# RASPBERRY_SHILED_ADS1299.net
KiCad netlist of a schematic drawn in Altium Designer
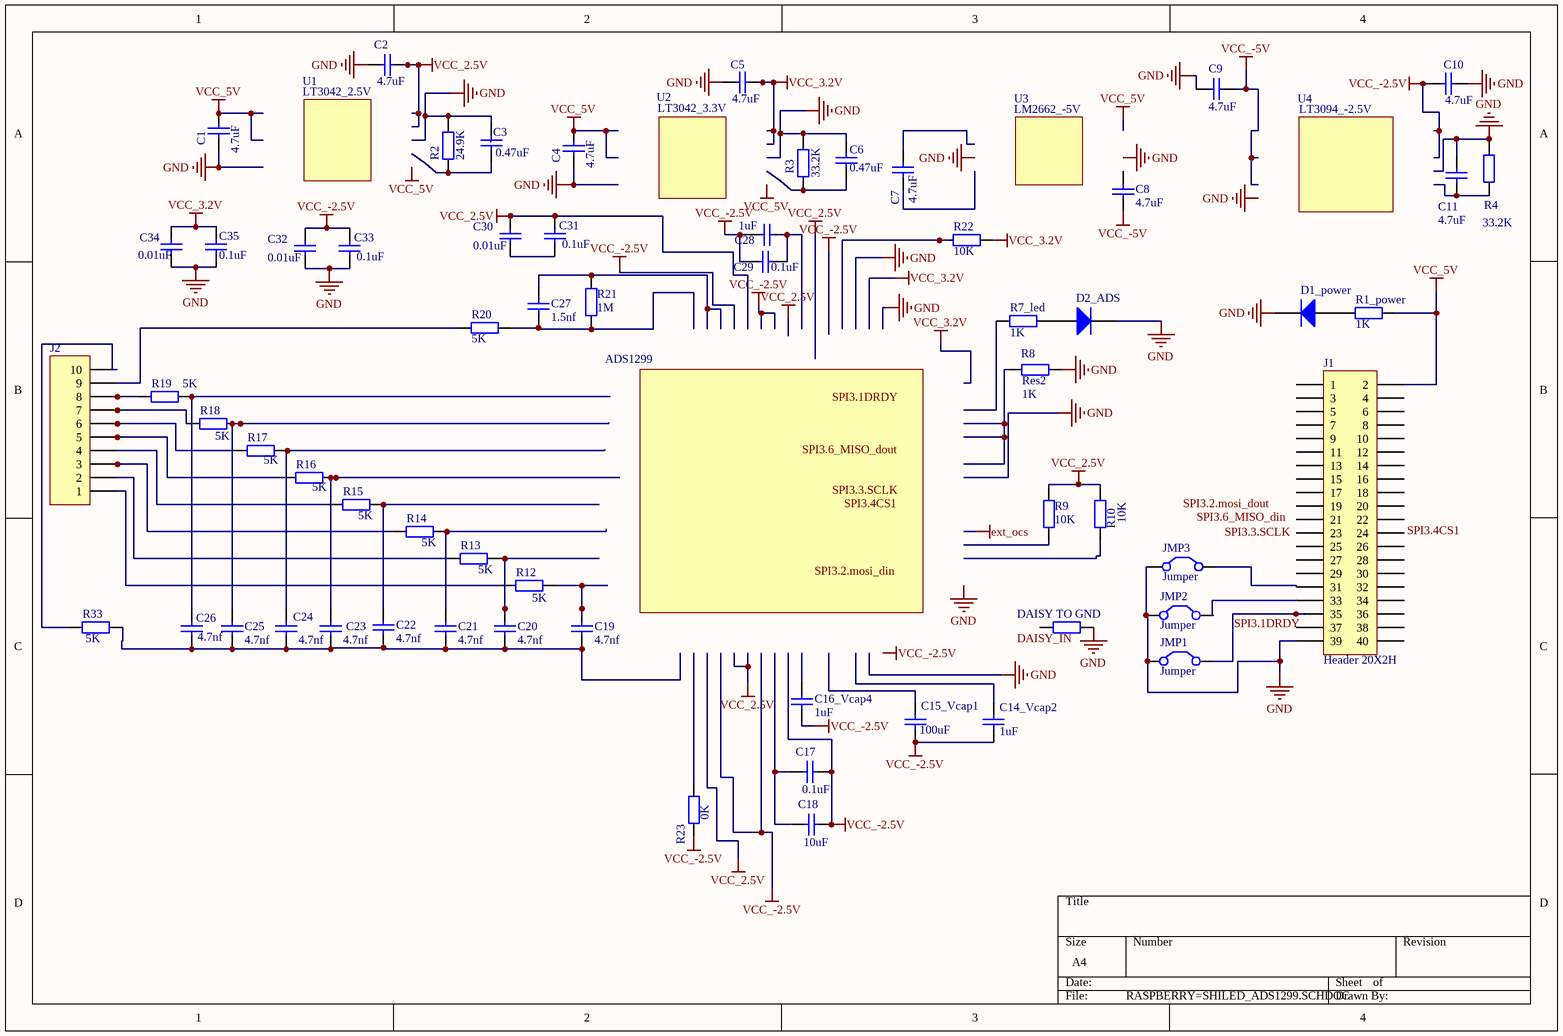
[diagram p0: RASPBERRY=SHILED_ADS1299.SCHDOC]

(export (version "E")
  (design (tool "Eeschema 10.0.6"))
  (components
    (comp (ref "C1")
      (value "4.7uF")
      (footprint "RAD-0.3")
      (description "Capacitor")
      (fields (field (name "PUBLISHER") "Altium Limited"))
      (libsource (lib "Miscellaneous Devices") (part "Cap"))
    )
    (comp (ref "C2")
      (value "4.7uF")
      (footprint "RAD-0.3")
      (description "Capacitor")
      (fields (field (name "PUBLISHER") "Altium Limited"))
      (libsource (lib "Miscellaneous Devices") (part "Cap"))
    )
    (comp (ref "C3")
      (value "0.47uF")
      (footprint "RAD-0.3")
      (description "Capacitor")
      (fields (field (name "PUBLISHER") "Altium Limited"))
      (libsource (lib "Miscellaneous Devices") (part "Cap"))
    )
    (comp (ref "C4")
      (value "4.7uF")
      (footprint "RAD-0.3")
      (description "Capacitor")
      (fields (field (name "PUBLISHER") "Altium Limited"))
      (libsource (lib "Miscellaneous Devices") (part "Cap"))
    )
    (comp (ref "C5")
      (value "4.7uF")
      (footprint "RAD-0.3")
      (description "Capacitor")
      (fields (field (name "PUBLISHER") "Altium Limited"))
      (libsource (lib "Miscellaneous Devices") (part "Cap"))
    )
    (comp (ref "C6")
      (value "0.47uF")
      (footprint "RAD-0.3")
      (description "Capacitor")
      (fields (field (name "PUBLISHER") "Altium Limited"))
      (libsource (lib "Miscellaneous Devices") (part "Cap"))
    )
    (comp (ref "C7")
      (value "4.7uF")
      (footprint "RAD-0.3")
      (description "Capacitor")
      (fields (field (name "PUBLISHER") "Altium Limited"))
      (libsource (lib "Miscellaneous Devices") (part "Cap"))
    )
    (comp (ref "C8")
      (value "4.7uF")
      (footprint "RAD-0.3")
      (description "Capacitor")
      (fields (field (name "PUBLISHER") "Altium Limited"))
      (libsource (lib "Miscellaneous Devices") (part "Cap"))
    )
    (comp (ref "C9")
      (value "4.7uF")
      (footprint "RAD-0.3")
      (description "Capacitor")
      (fields (field (name "PUBLISHER") "Altium Limited"))
      (libsource (lib "Miscellaneous Devices") (part "Cap"))
    )
    (comp (ref "C10")
      (value "4.7uF")
      (footprint "RAD-0.3")
      (description "Capacitor")
      (fields (field (name "PUBLISHER") "Altium Limited"))
      (libsource (lib "Miscellaneous Devices") (part "Cap"))
    )
    (comp (ref "C11")
      (value "4.7uF")
      (footprint "RAD-0.3")
      (description "Capacitor")
      (fields (field (name "PUBLISHER") "Altium Limited"))
      (libsource (lib "Miscellaneous Devices") (part "Cap"))
    )
    (comp (ref "C14_Vcap2")
      (value "1uF")
      (footprint "RAD-0.3")
      (description "Capacitor")
      (fields (field (name "PUBLISHER") "Altium Limited"))
      (libsource (lib "Miscellaneous Devices") (part "Cap"))
    )
    (comp (ref "C15_Vcap1")
      (value "100uF")
      (footprint "RAD-0.3")
      (description "Capacitor")
      (fields (field (name "PUBLISHER") "Altium Limited"))
      (libsource (lib "Miscellaneous Devices") (part "Cap"))
    )
    (comp (ref "C16_Vcap4")
      (value "1uF")
      (footprint "RAD-0.3")
      (description "Capacitor")
      (fields (field (name "PUBLISHER") "Altium Limited"))
      (libsource (lib "Miscellaneous Devices") (part "Cap"))
    )
    (comp (ref "C17")
      (value "0.1uF")
      (footprint "RAD-0.3")
      (description "Capacitor")
      (fields (field (name "PUBLISHER") "Altium Limited"))
      (libsource (lib "Miscellaneous Devices") (part "Cap"))
    )
    (comp (ref "C18")
      (value "10uF")
      (footprint "RAD-0.3")
      (description "Capacitor")
      (fields (field (name "PUBLISHER") "Altium Limited"))
      (libsource (lib "Miscellaneous Devices") (part "Cap"))
    )
    (comp (ref "C19")
      (value "4.7nf")
      (footprint "RAD-0.3")
      (description "Capacitor")
      (fields (field (name "PUBLISHER") "Altium Limited"))
      (libsource (lib "Miscellaneous Devices") (part "Cap"))
    )
    (comp (ref "C20")
      (value "4.7nf")
      (footprint "RAD-0.3")
      (description "Capacitor")
      (fields (field (name "PUBLISHER") "Altium Limited"))
      (libsource (lib "Miscellaneous Devices") (part "Cap"))
    )
    (comp (ref "C21")
      (value "4.7nf")
      (footprint "RAD-0.3")
      (description "Capacitor")
      (fields (field (name "PUBLISHER") "Altium Limited"))
      (libsource (lib "Miscellaneous Devices") (part "Cap"))
    )
    (comp (ref "C22")
      (value "4.7nf")
      (footprint "RAD-0.3")
      (description "Capacitor")
      (fields (field (name "PUBLISHER") "Altium Limited"))
      (libsource (lib "Miscellaneous Devices") (part "Cap"))
    )
    (comp (ref "C23")
      (value "4.7nf")
      (footprint "RAD-0.3")
      (description "Capacitor")
      (fields (field (name "PUBLISHER") "Altium Limited"))
      (libsource (lib "Miscellaneous Devices") (part "Cap"))
    )
    (comp (ref "C24")
      (value "4.7nf")
      (footprint "RAD-0.3")
      (description "Capacitor")
      (fields (field (name "PUBLISHER") "Altium Limited"))
      (libsource (lib "Miscellaneous Devices") (part "Cap"))
    )
    (comp (ref "C25")
      (value "4.7nf")
      (footprint "RAD-0.3")
      (description "Capacitor")
      (fields (field (name "PUBLISHER") "Altium Limited"))
      (libsource (lib "Miscellaneous Devices") (part "Cap"))
    )
    (comp (ref "C26")
      (value "4.7nf")
      (footprint "RAD-0.3")
      (description "Capacitor")
      (fields (field (name "PUBLISHER") "Altium Limited"))
      (libsource (lib "Miscellaneous Devices") (part "Cap"))
    )
    (comp (ref "C27")
      (value "1.5nf")
      (footprint "RAD-0.3")
      (description "Capacitor")
      (fields (field (name "PUBLISHER") "Altium Limited"))
      (libsource (lib "Miscellaneous Devices") (part "Cap"))
    )
    (comp (ref "C28")
      (value "1uF")
      (footprint "RAD-0.3")
      (description "Capacitor")
      (fields (field (name "PUBLISHER") "Altium Limited"))
      (libsource (lib "Miscellaneous Devices") (part "Cap"))
    )
    (comp (ref "C29")
      (value "0.1uF")
      (footprint "RAD-0.3")
      (description "Capacitor")
      (fields (field (name "PUBLISHER") "Altium Limited"))
      (libsource (lib "Miscellaneous Devices") (part "Cap"))
    )
    (comp (ref "C30")
      (value "0.1uF")
      (footprint "RAD-0.3")
      (description "Capacitor")
      (fields (field (name "PUBLISHER") "Altium Limited"))
      (libsource (lib "Miscellaneous Devices") (part "Cap"))
    )
    (comp (ref "C31")
      (value "0.01uF")
      (footprint "RAD-0.3")
      (description "Capacitor")
      (fields (field (name "PUBLISHER") "Altium Limited"))
      (libsource (lib "Miscellaneous Devices") (part "Cap"))
    )
    (comp (ref "C32")
      (value "0.1uF")
      (footprint "RAD-0.3")
      (description "Capacitor")
      (fields (field (name "PUBLISHER") "Altium Limited"))
      (libsource (lib "Miscellaneous Devices") (part "Cap"))
    )
    (comp (ref "C33")
      (value "0.01uF")
      (footprint "RAD-0.3")
      (description "Capacitor")
      (fields (field (name "PUBLISHER") "Altium Limited"))
      (libsource (lib "Miscellaneous Devices") (part "Cap"))
    )
    (comp (ref "C34")
      (value "0.1uF")
      (footprint "RAD-0.3")
      (description "Capacitor")
      (fields (field (name "PUBLISHER") "Altium Limited"))
      (libsource (lib "Miscellaneous Devices") (part "Cap"))
    )
    (comp (ref "C35")
      (value "0.01uF")
      (footprint "RAD-0.3")
      (description "Capacitor")
      (fields (field (name "PUBLISHER") "Altium Limited"))
      (libsource (lib "Miscellaneous Devices") (part "Cap"))
    )
    (comp (ref "D1_power")
      (value "~")
      (footprint "SMC")
      (description "Default Diode")
      (fields (field (name "PUBLISHER") "Altium Limited"))
      (libsource (lib "Miscellaneous Devices") (part "Diode"))
    )
    (comp (ref "D2_ADS")
      (value "~")
      (footprint "SMC")
      (description "Default Diode")
      (fields (field (name "PUBLISHER") "Altium Limited"))
      (libsource (lib "Miscellaneous Devices") (part "Diode"))
    )
    (comp (ref "DAISY TO GND")
      (value "~")
      (footprint "AXIAL-0.4")
      (description "Resistor")
      (fields (field (name "PUBLISHER") "Altium Limited"))
      (libsource (lib "Miscellaneous Devices") (part "Res2"))
    )
    (comp (ref "J1")
      (value "Header 20X2H")
      (footprint "HDR2X20H")
      (description "Header, 20-Pin, Dual row, Right Angle")
      (fields (field (name "PUBLISHER") "Altium Limited"))
      (libsource (lib "Miscellaneous Connectors") (part "Header 20X2H"))
    )
    (comp (ref "J2")
      (value "~")
      (footprint "HDR1X10")
      (description "Header, 10-Pin")
      (fields (field (name "PUBLISHER") "Altium Limited"))
      (libsource (lib "Miscellaneous Connectors") (part "Header 10"))
    )
    (comp (ref "JMP1")
      (value "Jumper")
      (footprint "RAD-0.2")
      (description "Jumper Wire")
      (fields (field (name "PUBLISHER") "Altium Limited"))
      (libsource (lib "Miscellaneous Devices") (part "Jumper"))
    )
    (comp (ref "JMP2")
      (value "Jumper")
      (footprint "RAD-0.2")
      (description "Jumper Wire")
      (fields (field (name "PUBLISHER") "Altium Limited"))
      (libsource (lib "Miscellaneous Devices") (part "Jumper"))
    )
    (comp (ref "JMP3")
      (value "Jumper")
      (footprint "RAD-0.2")
      (description "Jumper Wire")
      (fields (field (name "PUBLISHER") "Altium Limited"))
      (libsource (lib "Miscellaneous Devices") (part "Jumper"))
    )
    (comp (ref "R1_power")
      (value "1K")
      (footprint "AXIAL-0.4")
      (description "Resistor")
      (fields (field (name "PUBLISHER") "Altium Limited"))
      (libsource (lib "Miscellaneous Devices") (part "Res2"))
    )
    (comp (ref "R2")
      (value "24.9K")
      (footprint "AXIAL-0.4")
      (description "Resistor")
      (fields (field (name "PUBLISHER") "Altium Limited"))
      (libsource (lib "") (part "Res2_1"))
    )
    (comp (ref "R3")
      (value "33.2K")
      (footprint "AXIAL-0.4")
      (description "Resistor")
      (fields (field (name "PUBLISHER") "Altium Limited"))
      (libsource (lib "") (part "Res2_1"))
    )
    (comp (ref "R4")
      (value "33.2K")
      (footprint "AXIAL-0.4")
      (description "Resistor")
      (fields (field (name "PUBLISHER") "Altium Limited"))
      (libsource (lib "") (part "Res2_1"))
    )
    (comp (ref "R7_led")
      (value "1K")
      (footprint "AXIAL-0.4")
      (description "Resistor")
      (fields (field (name "PUBLISHER") "Altium Limited"))
      (libsource (lib "") (part "Res2_2"))
    )
    (comp (ref "R8")
      (value "Res2")
      (footprint "AXIAL-0.4")
      (description "Resistor")
      (fields (field (name "ALTIUM_VALUE") "1K") (field (name "PUBLISHER") "Altium Limited"))
      (libsource (lib "Miscellaneous Devices") (part "Res2"))
    )
    (comp (ref "R9")
      (value "10K")
      (footprint "AXIAL-0.4")
      (description "Resistor")
      (fields (field (name "PUBLISHER") "Altium Limited"))
      (libsource (lib "") (part "Res2_3"))
    )
    (comp (ref "R10")
      (value "10K")
      (footprint "AXIAL-0.4")
      (description "Resistor")
      (fields (field (name "PUBLISHER") "Altium Limited"))
      (libsource (lib "") (part "Res2_1"))
    )
    (comp (ref "R12")
      (value "5K")
      (footprint "AXIAL-0.4")
      (description "Resistor")
      (fields (field (name "PUBLISHER") "Altium Limited"))
      (libsource (lib "Miscellaneous Devices") (part "Res2"))
    )
    (comp (ref "R13")
      (value "5K")
      (footprint "AXIAL-0.4")
      (description "Resistor")
      (fields (field (name "PUBLISHER") "Altium Limited"))
      (libsource (lib "Miscellaneous Devices") (part "Res2"))
    )
    (comp (ref "R14")
      (value "5K")
      (footprint "AXIAL-0.4")
      (description "Resistor")
      (fields (field (name "PUBLISHER") "Altium Limited"))
      (libsource (lib "Miscellaneous Devices") (part "Res2"))
    )
    (comp (ref "R15")
      (value "5K")
      (footprint "AXIAL-0.4")
      (description "Resistor")
      (fields (field (name "PUBLISHER") "Altium Limited"))
      (libsource (lib "Miscellaneous Devices") (part "Res2"))
    )
    (comp (ref "R16")
      (value "5K")
      (footprint "AXIAL-0.4")
      (description "Resistor")
      (fields (field (name "PUBLISHER") "Altium Limited"))
      (libsource (lib "Miscellaneous Devices") (part "Res2"))
    )
    (comp (ref "R17")
      (value "5K")
      (footprint "AXIAL-0.4")
      (description "Resistor")
      (fields (field (name "PUBLISHER") "Altium Limited"))
      (libsource (lib "Miscellaneous Devices") (part "Res2"))
    )
    (comp (ref "R18")
      (value "5K")
      (footprint "AXIAL-0.4")
      (description "Resistor")
      (fields (field (name "PUBLISHER") "Altium Limited"))
      (libsource (lib "Miscellaneous Devices") (part "Res2"))
    )
    (comp (ref "R19")
      (value "5K")
      (footprint "AXIAL-0.4")
      (description "Resistor")
      (fields (field (name "PUBLISHER") "Altium Limited"))
      (libsource (lib "Miscellaneous Devices") (part "Res2"))
    )
    (comp (ref "R20")
      (value "5K")
      (footprint "AXIAL-0.4")
      (description "Resistor")
      (fields (field (name "PUBLISHER") "Altium Limited"))
      (libsource (lib "Miscellaneous Devices") (part "Res2"))
    )
    (comp (ref "R21")
      (value "1M")
      (footprint "AXIAL-0.4")
      (description "Resistor")
      (fields (field (name "PUBLISHER") "Altium Limited"))
      (libsource (lib "") (part "Res2_1"))
    )
    (comp (ref "R22")
      (value "10K")
      (footprint "AXIAL-0.4")
      (description "Resistor")
      (fields (field (name "PUBLISHER") "Altium Limited"))
      (libsource (lib "") (part "Res2_2"))
    )
    (comp (ref "R23")
      (value "0K")
      (footprint "AXIAL-0.4")
      (description "Resistor")
      (fields (field (name "PUBLISHER") "Altium Limited"))
      (libsource (lib "") (part "Res2_1"))
    )
    (comp (ref "R33")
      (value "5K")
      (footprint "AXIAL-0.4")
      (description "Resistor")
      (fields (field (name "PUBLISHER") "Altium Limited"))
      (libsource (lib "Miscellaneous Devices") (part "Res2"))
    )
  )
  (nets
    (net (code "9") (name "GND") (class "Default")
      (node (ref "C1") (pin "1") (pinfunction "1_1") (pintype "passive"))
      (node (ref "C10") (pin "2") (pinfunction "2_2") (pintype "passive"))
      (node (ref "C11") (pin "2") (pinfunction "2_2") (pintype "passive"))
      (node (ref "C2") (pin "1") (pinfunction "1_1") (pintype "passive"))
      (node (ref "C3") (pin "2") (pinfunction "2_2") (pintype "passive"))
      (node (ref "C32") (pin "1") (pinfunction "1_1") (pintype "passive"))
      (node (ref "C33") (pin "1") (pinfunction "1_1") (pintype "passive"))
      (node (ref "C34") (pin "1") (pinfunction "1_1") (pintype "passive"))
      (node (ref "C35") (pin "1") (pinfunction "1_1") (pintype "passive"))
      (node (ref "C4") (pin "1") (pinfunction "1_1") (pintype "passive"))
      (node (ref "C5") (pin "1") (pinfunction "1_1") (pintype "passive"))
      (node (ref "C6") (pin "2") (pinfunction "2_2") (pintype "passive"))
      (node (ref "C9") (pin "1") (pinfunction "1_1") (pintype "passive"))
      (node (ref "D1_power") (pin "2") (pinfunction "K_2") (pintype "passive"))
      (node (ref "D2_ADS") (pin "2") (pinfunction "K_2") (pintype "passive"))
      (node (ref "DAISY TO GND") (pin "2") (pinfunction "2_2") (pintype "passive"))
      (node (ref "J1") (pin "39") (pinfunction "39_39") (pintype "passive"))
      (node (ref "JMP1") (pin "1") (pinfunction "C1_1") (pintype "passive"))
      (node (ref "JMP2") (pin "1") (pinfunction "C1_1") (pintype "passive"))
      (node (ref "JMP3") (pin "1") (pinfunction "C1_1") (pintype "passive"))
      (node (ref "R4") (pin "2") (pinfunction "2_2") (pintype "passive"))
      (node (ref "R8") (pin "2") (pinfunction "2_2") (pintype "passive"))
    )
    (net (code "10") (name "Net-(C3-Pad1)") (class "Default")
      (node (ref "C3") (pin "1") (pinfunction "1_1") (pintype "passive"))
      (node (ref "R2") (pin "1") (pinfunction "1_1") (pintype "passive"))
    )
    (net (code "11") (name "Net-(C6-Pad1)") (class "Default")
      (node (ref "C6") (pin "1") (pinfunction "1_1") (pintype "passive"))
      (node (ref "R3") (pin "1") (pinfunction "1_1") (pintype "passive"))
    )
    (net (code "12") (name "Net-(C11-Pad1)") (class "Default")
      (node (ref "C11") (pin "1") (pinfunction "1_1") (pintype "passive"))
      (node (ref "R4") (pin "1") (pinfunction "1_1") (pintype "passive"))
    )
    (net (code "13") (name "Net-(C17-Pad1)") (class "Default")
      (node (ref "C17") (pin "1") (pinfunction "1_1") (pintype "passive"))
      (node (ref "C18") (pin "1") (pinfunction "1_1") (pintype "passive"))
    )
    (net (code "14") (name "Net-(C19-Pad1)") (class "Default")
      (node (ref "C19") (pin "1") (pinfunction "1_1") (pintype "passive"))
      (node (ref "R12") (pin "2") (pinfunction "2_2") (pintype "passive"))
    )
    (net (code "15") (name "Net-(C19-Pad2)") (class "Default")
      (node (ref "C19") (pin "2") (pinfunction "2_2") (pintype "passive"))
      (node (ref "C20") (pin "2") (pinfunction "2_2") (pintype "passive"))
      (node (ref "C21") (pin "2") (pinfunction "2_2") (pintype "passive"))
      (node (ref "C22") (pin "2") (pinfunction "2_2") (pintype "passive"))
      (node (ref "C23") (pin "2") (pinfunction "2_2") (pintype "passive"))
      (node (ref "C24") (pin "2") (pinfunction "2_2") (pintype "passive"))
      (node (ref "C25") (pin "1") (pinfunction "1_1") (pintype "passive"))
      (node (ref "C26") (pin "2") (pinfunction "2_2") (pintype "passive"))
      (node (ref "R33") (pin "2") (pinfunction "2_2") (pintype "passive"))
    )
    (net (code "16") (name "Net-(C20-Pad1)") (class "Default")
      (node (ref "C20") (pin "1") (pinfunction "1_1") (pintype "passive"))
      (node (ref "R13") (pin "2") (pinfunction "2_2") (pintype "passive"))
    )
    (net (code "17") (name "Net-(C21-Pad1)") (class "Default")
      (node (ref "C21") (pin "1") (pinfunction "1_1") (pintype "passive"))
      (node (ref "R14") (pin "2") (pinfunction "2_2") (pintype "passive"))
    )
    (net (code "18") (name "Net-(C22-Pad1)") (class "Default")
      (node (ref "C22") (pin "1") (pinfunction "1_1") (pintype "passive"))
      (node (ref "R15") (pin "2") (pinfunction "2_2") (pintype "passive"))
    )
    (net (code "19") (name "Net-(C23-Pad1)") (class "Default")
      (node (ref "C23") (pin "1") (pinfunction "1_1") (pintype "passive"))
      (node (ref "R16") (pin "2") (pinfunction "2_2") (pintype "passive"))
    )
    (net (code "20") (name "Net-(C24-Pad1)") (class "Default")
      (node (ref "C24") (pin "1") (pinfunction "1_1") (pintype "passive"))
      (node (ref "R17") (pin "2") (pinfunction "2_2") (pintype "passive"))
    )
    (net (code "21") (name "Net-(C25-Pad2)") (class "Default")
      (node (ref "C25") (pin "2") (pinfunction "2_2") (pintype "passive"))
      (node (ref "R18") (pin "2") (pinfunction "2_2") (pintype "passive"))
    )
    (net (code "22") (name "Net-(C26-Pad1)") (class "Default")
      (node (ref "C26") (pin "1") (pinfunction "1_1") (pintype "passive"))
      (node (ref "R19") (pin "2") (pinfunction "2_2") (pintype "passive"))
    )
    (net (code "23") (name "Net-(C27-Pad1)") (class "Default")
      (node (ref "C27") (pin "1") (pinfunction "1_1") (pintype "passive"))
      (node (ref "R20") (pin "2") (pinfunction "2_2") (pintype "passive"))
      (node (ref "R21") (pin "1") (pinfunction "1_1") (pintype "passive"))
    )
    (net (code "24") (name "Net-(C27-Pad2)") (class "Default")
      (node (ref "C27") (pin "2") (pinfunction "2_2") (pintype "passive"))
      (node (ref "R21") (pin "2") (pinfunction "2_2") (pintype "passive"))
    )
    (net (code "25") (name "Net-(C28-Pad2)") (class "Default")
      (node (ref "C28") (pin "2") (pinfunction "2_2") (pintype "passive"))
      (node (ref "C29") (pin "2") (pinfunction "2_2") (pintype "passive"))
    )
    (net (code "26") (name "Net-(C30-Pad1)") (class "Default")
      (node (ref "C30") (pin "1") (pinfunction "1_1") (pintype "passive"))
      (node (ref "C31") (pin "1") (pinfunction "1_1") (pintype "passive"))
    )
    (net (code "27") (name "Net-(D1_power-A)") (class "Default")
      (node (ref "D1_power") (pin "1") (pinfunction "A_1") (pintype "passive"))
      (node (ref "R1_power") (pin "1") (pinfunction "1_1") (pintype "passive"))
    )
    (net (code "28") (name "Net-(D2_ADS-A)") (class "Default")
      (node (ref "D2_ADS") (pin "1") (pinfunction "A_1") (pintype "passive"))
      (node (ref "R7_led") (pin "1") (pinfunction "1_1") (pintype "passive"))
    )
    (net (code "29") (name "Net-(J2-Pad1)") (class "Default")
      (node (ref "J2") (pin "1") (pinfunction "1_1") (pintype "passive"))
      (node (ref "R12") (pin "1") (pinfunction "1_1") (pintype "passive"))
    )
    (net (code "30") (name "Net-(J2-Pad2)") (class "Default")
      (node (ref "J2") (pin "2") (pinfunction "2_2") (pintype "passive"))
      (node (ref "R13") (pin "1") (pinfunction "1_1") (pintype "passive"))
    )
    (net (code "31") (name "Net-(J2-Pad3)") (class "Default")
      (node (ref "J2") (pin "3") (pinfunction "3_3") (pintype "passive"))
      (node (ref "R14") (pin "1") (pinfunction "1_1") (pintype "passive"))
    )
    (net (code "32") (name "Net-(J2-Pad4)") (class "Default")
      (node (ref "J2") (pin "4") (pinfunction "4_4") (pintype "passive"))
      (node (ref "R15") (pin "1") (pinfunction "1_1") (pintype "passive"))
    )
    (net (code "33") (name "Net-(J2-Pad5)") (class "Default")
      (node (ref "J2") (pin "5") (pinfunction "5_5") (pintype "passive"))
      (node (ref "R16") (pin "1") (pinfunction "1_1") (pintype "passive"))
    )
    (net (code "34") (name "Net-(J2-Pad6)") (class "Default")
      (node (ref "J2") (pin "6") (pinfunction "6_6") (pintype "passive"))
      (node (ref "R17") (pin "1") (pinfunction "1_1") (pintype "passive"))
    )
    (net (code "35") (name "Net-(J2-Pad7)") (class "Default")
      (node (ref "J2") (pin "7") (pinfunction "7_7") (pintype "passive"))
      (node (ref "R18") (pin "1") (pinfunction "1_1") (pintype "passive"))
    )
    (net (code "36") (name "Net-(J2-Pad8)") (class "Default")
      (node (ref "J2") (pin "8") (pinfunction "8_8") (pintype "passive"))
      (node (ref "R19") (pin "1") (pinfunction "1_1") (pintype "passive"))
    )
    (net (code "37") (name "Net-(J2-Pad9)") (class "Default")
      (node (ref "J2") (pin "9") (pinfunction "9_9") (pintype "passive"))
      (node (ref "R20") (pin "1") (pinfunction "1_1") (pintype "passive"))
    )
    (net (code "38") (name "Net-(J2-Pad10)") (class "Default")
      (node (ref "J2") (pin "10") (pinfunction "10_10") (pintype "passive"))
      (node (ref "R33") (pin "1") (pinfunction "1_1") (pintype "passive"))
    )
    (net (code "39") (name "Net-(JMP1-C2)") (class "Default")
      (node (ref "J1") (pin "35") (pinfunction "35_35") (pintype "passive"))
      (node (ref "JMP1") (pin "2") (pinfunction "C2_2") (pintype "passive"))
    )
    (net (code "40") (name "Net-(JMP2-C2)") (class "Default")
      (node (ref "J1") (pin "33") (pinfunction "33_33") (pintype "passive"))
      (node (ref "JMP2") (pin "2") (pinfunction "C2_2") (pintype "passive"))
    )
    (net (code "41") (name "Net-(JMP3-C2)") (class "Default")
      (node (ref "J1") (pin "31") (pinfunction "31_31") (pintype "passive"))
      (node (ref "JMP3") (pin "2") (pinfunction "C2_2") (pintype "passive"))
    )
    (net (code "42") (name "VCC_-2.5V") (class "Default")
      (node (ref "C10") (pin "1") (pinfunction "1_1") (pintype "passive"))
      (node (ref "C14_Vcap2") (pin "1") (pinfunction "1_1") (pintype "passive"))
      (node (ref "C15_Vcap1") (pin "1") (pinfunction "1_1") (pintype "passive"))
      (node (ref "C16_Vcap4") (pin "1") (pinfunction "1_1") (pintype "passive"))
      (node (ref "C17") (pin "2") (pinfunction "2_2") (pintype "passive"))
      (node (ref "C18") (pin "2") (pinfunction "2_2") (pintype "passive"))
      (node (ref "C28") (pin "1") (pinfunction "1_1") (pintype "passive"))
      (node (ref "C29") (pin "1") (pinfunction "1_1") (pintype "passive"))
      (node (ref "C32") (pin "2") (pinfunction "2_2") (pintype "passive"))
      (node (ref "C33") (pin "2") (pinfunction "2_2") (pintype "passive"))
      (node (ref "R23") (pin "1") (pinfunction "1_1") (pintype "passive"))
    )
    (net (code "43") (name "VCC_-5V") (class "Default")
      (node (ref "C8") (pin "1") (pinfunction "1_1") (pintype "passive"))
      (node (ref "C9") (pin "2") (pinfunction "2_2") (pintype "passive"))
    )
    (net (code "44") (name "VCC_2.5V") (class "Default")
      (node (ref "C2") (pin "2") (pinfunction "2_2") (pintype "passive"))
      (node (ref "C30") (pin "2") (pinfunction "2_2") (pintype "passive"))
      (node (ref "C31") (pin "2") (pinfunction "2_2") (pintype "passive"))
      (node (ref "R10") (pin "2") (pinfunction "2_2") (pintype "passive"))
      (node (ref "R9") (pin "1") (pinfunction "1_1") (pintype "passive"))
    )
    (net (code "45") (name "VCC_3.2V") (class "Default")
      (node (ref "C34") (pin "2") (pinfunction "2_2") (pintype "passive"))
      (node (ref "C35") (pin "2") (pinfunction "2_2") (pintype "passive"))
      (node (ref "C5") (pin "2") (pinfunction "2_2") (pintype "passive"))
      (node (ref "R22") (pin "1") (pinfunction "1_1") (pintype "passive"))
    )
    (net (code "46") (name "VCC_5V") (class "Default")
      (node (ref "C1") (pin "2") (pinfunction "2_2") (pintype "passive"))
      (node (ref "C4") (pin "2") (pinfunction "2_2") (pintype "passive"))
      (node (ref "J1") (pin "2") (pinfunction "2_2") (pintype "passive"))
      (node (ref "R1_power") (pin "2") (pinfunction "2_2") (pintype "passive"))
    )
    (net (code "48") (name "unconnected-(C7-Pad1)") (class "Default")
      (node (ref "C7") (pin "1") (pinfunction "1_1") (pintype "passive"))
    )
    (net (code "49") (name "unconnected-(C7-Pad2)") (class "Default")
      (node (ref "C7") (pin "2") (pinfunction "2_2") (pintype "passive"))
    )
    (net (code "50") (name "unconnected-(C8-Pad2)") (class "Default")
      (node (ref "C8") (pin "2") (pinfunction "2_2") (pintype "passive"))
    )
    (net (code "51") (name "unconnected-(C14_Vcap2-Pad2)") (class "Default")
      (node (ref "C14_Vcap2") (pin "2") (pinfunction "2_2") (pintype "passive"))
    )
    (net (code "52") (name "unconnected-(C15_Vcap1-Pad2)") (class "Default")
      (node (ref "C15_Vcap1") (pin "2") (pinfunction "2_2") (pintype "passive"))
    )
    (net (code "53") (name "unconnected-(C16_Vcap4-Pad2)") (class "Default")
      (node (ref "C16_Vcap4") (pin "2") (pinfunction "2_2") (pintype "passive"))
    )
    (net (code "54") (name "unconnected-(DAISY TO GND-Pad1)") (class "Default")
      (node (ref "DAISY TO GND") (pin "1") (pinfunction "1_1") (pintype "passive"))
    )
    (net (code "55") (name "unconnected-(J1-Pad1)") (class "Default")
      (node (ref "J1") (pin "1") (pinfunction "1_1") (pintype "passive"))
    )
    (net (code "56") (name "unconnected-(J1-Pad3)") (class "Default")
      (node (ref "J1") (pin "3") (pinfunction "3_3") (pintype "passive"))
    )
    (net (code "57") (name "unconnected-(J1-Pad4)") (class "Default")
      (node (ref "J1") (pin "4") (pinfunction "4_4") (pintype "passive"))
    )
    (net (code "58") (name "unconnected-(J1-Pad5)") (class "Default")
      (node (ref "J1") (pin "5") (pinfunction "5_5") (pintype "passive"))
    )
    (net (code "59") (name "unconnected-(J1-Pad6)") (class "Default")
      (node (ref "J1") (pin "6") (pinfunction "6_6") (pintype "passive"))
    )
    (net (code "60") (name "unconnected-(J1-Pad7)") (class "Default")
      (node (ref "J1") (pin "7") (pinfunction "7_7") (pintype "passive"))
    )
    (net (code "61") (name "unconnected-(J1-Pad8)") (class "Default")
      (node (ref "J1") (pin "8") (pinfunction "8_8") (pintype "passive"))
    )
    (net (code "62") (name "unconnected-(J1-Pad9)") (class "Default")
      (node (ref "J1") (pin "9") (pinfunction "9_9") (pintype "passive"))
    )
    (net (code "63") (name "unconnected-(J1-Pad10)") (class "Default")
      (node (ref "J1") (pin "10") (pinfunction "10_10") (pintype "passive"))
    )
    (net (code "64") (name "unconnected-(J1-Pad11)") (class "Default")
      (node (ref "J1") (pin "11") (pinfunction "11_11") (pintype "passive"))
    )
    (net (code "65") (name "unconnected-(J1-Pad12)") (class "Default")
      (node (ref "J1") (pin "12") (pinfunction "12_12") (pintype "passive"))
    )
    (net (code "66") (name "unconnected-(J1-Pad13)") (class "Default")
      (node (ref "J1") (pin "13") (pinfunction "13_13") (pintype "passive"))
    )
    (net (code "67") (name "unconnected-(J1-Pad14)") (class "Default")
      (node (ref "J1") (pin "14") (pinfunction "14_14") (pintype "passive"))
    )
    (net (code "68") (name "unconnected-(J1-Pad15)") (class "Default")
      (node (ref "J1") (pin "15") (pinfunction "15_15") (pintype "passive"))
    )
    (net (code "69") (name "unconnected-(J1-Pad16)") (class "Default")
      (node (ref "J1") (pin "16") (pinfunction "16_16") (pintype "passive"))
    )
    (net (code "70") (name "unconnected-(J1-Pad17)") (class "Default")
      (node (ref "J1") (pin "17") (pinfunction "17_17") (pintype "passive"))
    )
    (net (code "71") (name "unconnected-(J1-Pad18)") (class "Default")
      (node (ref "J1") (pin "18") (pinfunction "18_18") (pintype "passive"))
    )
    (net (code "72") (name "unconnected-(J1-Pad19)") (class "Default")
      (node (ref "J1") (pin "19") (pinfunction "19_19") (pintype "passive"))
    )
    (net (code "73") (name "unconnected-(J1-Pad20)") (class "Default")
      (node (ref "J1") (pin "20") (pinfunction "20_20") (pintype "passive"))
    )
    (net (code "74") (name "unconnected-(J1-Pad21)") (class "Default")
      (node (ref "J1") (pin "21") (pinfunction "21_21") (pintype "passive"))
    )
    (net (code "75") (name "unconnected-(J1-Pad22)") (class "Default")
      (node (ref "J1") (pin "22") (pinfunction "22_22") (pintype "passive"))
    )
    (net (code "76") (name "unconnected-(J1-Pad23)") (class "Default")
      (node (ref "J1") (pin "23") (pinfunction "23_23") (pintype "passive"))
    )
    (net (code "77") (name "unconnected-(J1-Pad24)") (class "Default")
      (node (ref "J1") (pin "24") (pinfunction "24_24") (pintype "passive"))
    )
    (net (code "78") (name "unconnected-(J1-Pad25)") (class "Default")
      (node (ref "J1") (pin "25") (pinfunction "25_25") (pintype "passive"))
    )
    (net (code "79") (name "unconnected-(J1-Pad26)") (class "Default")
      (node (ref "J1") (pin "26") (pinfunction "26_26") (pintype "passive"))
    )
    (net (code "80") (name "unconnected-(J1-Pad27)") (class "Default")
      (node (ref "J1") (pin "27") (pinfunction "27_27") (pintype "passive"))
    )
    (net (code "81") (name "unconnected-(J1-Pad28)") (class "Default")
      (node (ref "J1") (pin "28") (pinfunction "28_28") (pintype "passive"))
    )
    (net (code "82") (name "unconnected-(J1-Pad29)") (class "Default")
      (node (ref "J1") (pin "29") (pinfunction "29_29") (pintype "passive"))
    )
    (net (code "83") (name "unconnected-(J1-Pad30)") (class "Default")
      (node (ref "J1") (pin "30") (pinfunction "30_30") (pintype "passive"))
    )
    (net (code "84") (name "unconnected-(J1-Pad32)") (class "Default")
      (node (ref "J1") (pin "32") (pinfunction "32_32") (pintype "passive"))
    )
    (net (code "85") (name "unconnected-(J1-Pad34)") (class "Default")
      (node (ref "J1") (pin "34") (pinfunction "34_34") (pintype "passive"))
    )
    (net (code "86") (name "unconnected-(J1-Pad36)") (class "Default")
      (node (ref "J1") (pin "36") (pinfunction "36_36") (pintype "passive"))
    )
    (net (code "87") (name "unconnected-(J1-Pad37)") (class "Default")
      (node (ref "J1") (pin "37") (pinfunction "37_37") (pintype "passive"))
    )
    (net (code "88") (name "unconnected-(J1-Pad38)") (class "Default")
      (node (ref "J1") (pin "38") (pinfunction "38_38") (pintype "passive"))
    )
    (net (code "89") (name "unconnected-(J1-Pad40)") (class "Default")
      (node (ref "J1") (pin "40") (pinfunction "40_40") (pintype "passive"))
    )
    (net (code "90") (name "unconnected-(R2-Pad2)") (class "Default")
      (node (ref "R2") (pin "2") (pinfunction "2_2") (pintype "passive"))
    )
    (net (code "91") (name "unconnected-(R3-Pad2)") (class "Default")
      (node (ref "R3") (pin "2") (pinfunction "2_2") (pintype "passive"))
    )
    (net (code "92") (name "unconnected-(R7_led-Pad2)") (class "Default")
      (node (ref "R7_led") (pin "2") (pinfunction "2_2") (pintype "passive"))
    )
    (net (code "93") (name "unconnected-(R8-Pad1)") (class "Default")
      (node (ref "R8") (pin "1") (pinfunction "1_1") (pintype "passive"))
    )
    (net (code "94") (name "unconnected-(R9-Pad2)") (class "Default")
      (node (ref "R9") (pin "2") (pinfunction "2_2") (pintype "passive"))
    )
    (net (code "95") (name "unconnected-(R10-Pad1)") (class "Default")
      (node (ref "R10") (pin "1") (pinfunction "1_1") (pintype "passive"))
    )
    (net (code "96") (name "unconnected-(R22-Pad2)") (class "Default")
      (node (ref "R22") (pin "2") (pinfunction "2_2") (pintype "passive"))
    )
    (net (code "97") (name "unconnected-(R23-Pad2)") (class "Default")
      (node (ref "R23") (pin "2") (pinfunction "2_2") (pintype "passive"))
    )
  )
)
